# I2CShifter.net
KiCad netlist of a schematic drawn in Altium Designer
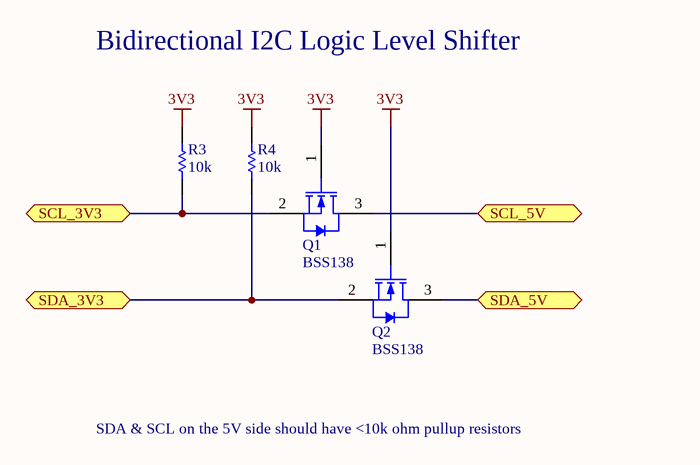
[diagram p0: I2CShifter.SchDoc]

(export (version "E")
  (design (tool "Eeschema 10.0.6"))
  (components
    (comp (ref "Q1")
      (value "BSS138")
      (footprint "FAIR-SOT23-3_V")
      (fields (field (name "TOLERANCE") "30ppm"))
      (libsource (lib "Altium Content Vault") (part "NEMOS-GSD-3"))
    )
    (comp (ref "Q2")
      (value "BSS138")
      (footprint "FAIR-SOT23-3_V")
      (fields (field (name "TOLERANCE") "30ppm"))
      (libsource (lib "Altium Content Vault") (part "NEMOS-GSD-3"))
    )
    (comp (ref "R3")
      (value "10k")
      (footprint "RESC0603(1608)_L")
      (description "10K 0.1W 5% 0603 (1608 Metric)  SMD")
      (fields (field (name "TOLERANCE") "5 %") (field (name "POWER") "0.1 W"))
      (libsource (lib "Altium Content Vault") (part "RES"))
    )
    (comp (ref "R4")
      (value "10k")
      (footprint "RESC0603(1608)_L")
      (description "10K 0.1W 5% 0603 (1608 Metric)  SMD")
      (fields (field (name "TOLERANCE") "5 %") (field (name "POWER") "0.1 W"))
      (libsource (lib "Altium Content Vault") (part "RES"))
    )
  )
  (nets
    (net (code "1") (name "/SCL_3V3") (class "Default")
      (node (ref "Q1") (pin "2") (pinfunction "S_2") (pintype "passive"))
      (node (ref "R3") (pin "1") (pinfunction "1_1") (pintype "passive"))
    )
    (net (code "2") (name "/SCL_5V") (class "Default")
      (node (ref "Q1") (pin "3") (pinfunction "D_3") (pintype "passive"))
    )
    (net (code "3") (name "/SDA_3V3") (class "Default")
      (node (ref "Q2") (pin "2") (pinfunction "S_2") (pintype "passive"))
      (node (ref "R4") (pin "1") (pinfunction "1_1") (pintype "passive"))
    )
    (net (code "4") (name "/SDA_5V") (class "Default")
      (node (ref "Q2") (pin "3") (pinfunction "D_3") (pintype "passive"))
    )
    (net (code "5") (name "3V3") (class "Default")
      (node (ref "Q1") (pin "1") (pinfunction "G_1") (pintype "passive"))
      (node (ref "Q2") (pin "1") (pinfunction "G_1") (pintype "passive"))
      (node (ref "R3") (pin "2") (pinfunction "2_2") (pintype "passive"))
      (node (ref "R4") (pin "2") (pinfunction "2_2") (pintype "passive"))
    )
  )
)
